# LVMi_Pressure_Sensor.net
KiCad netlist of a schematic drawn in EAGLE
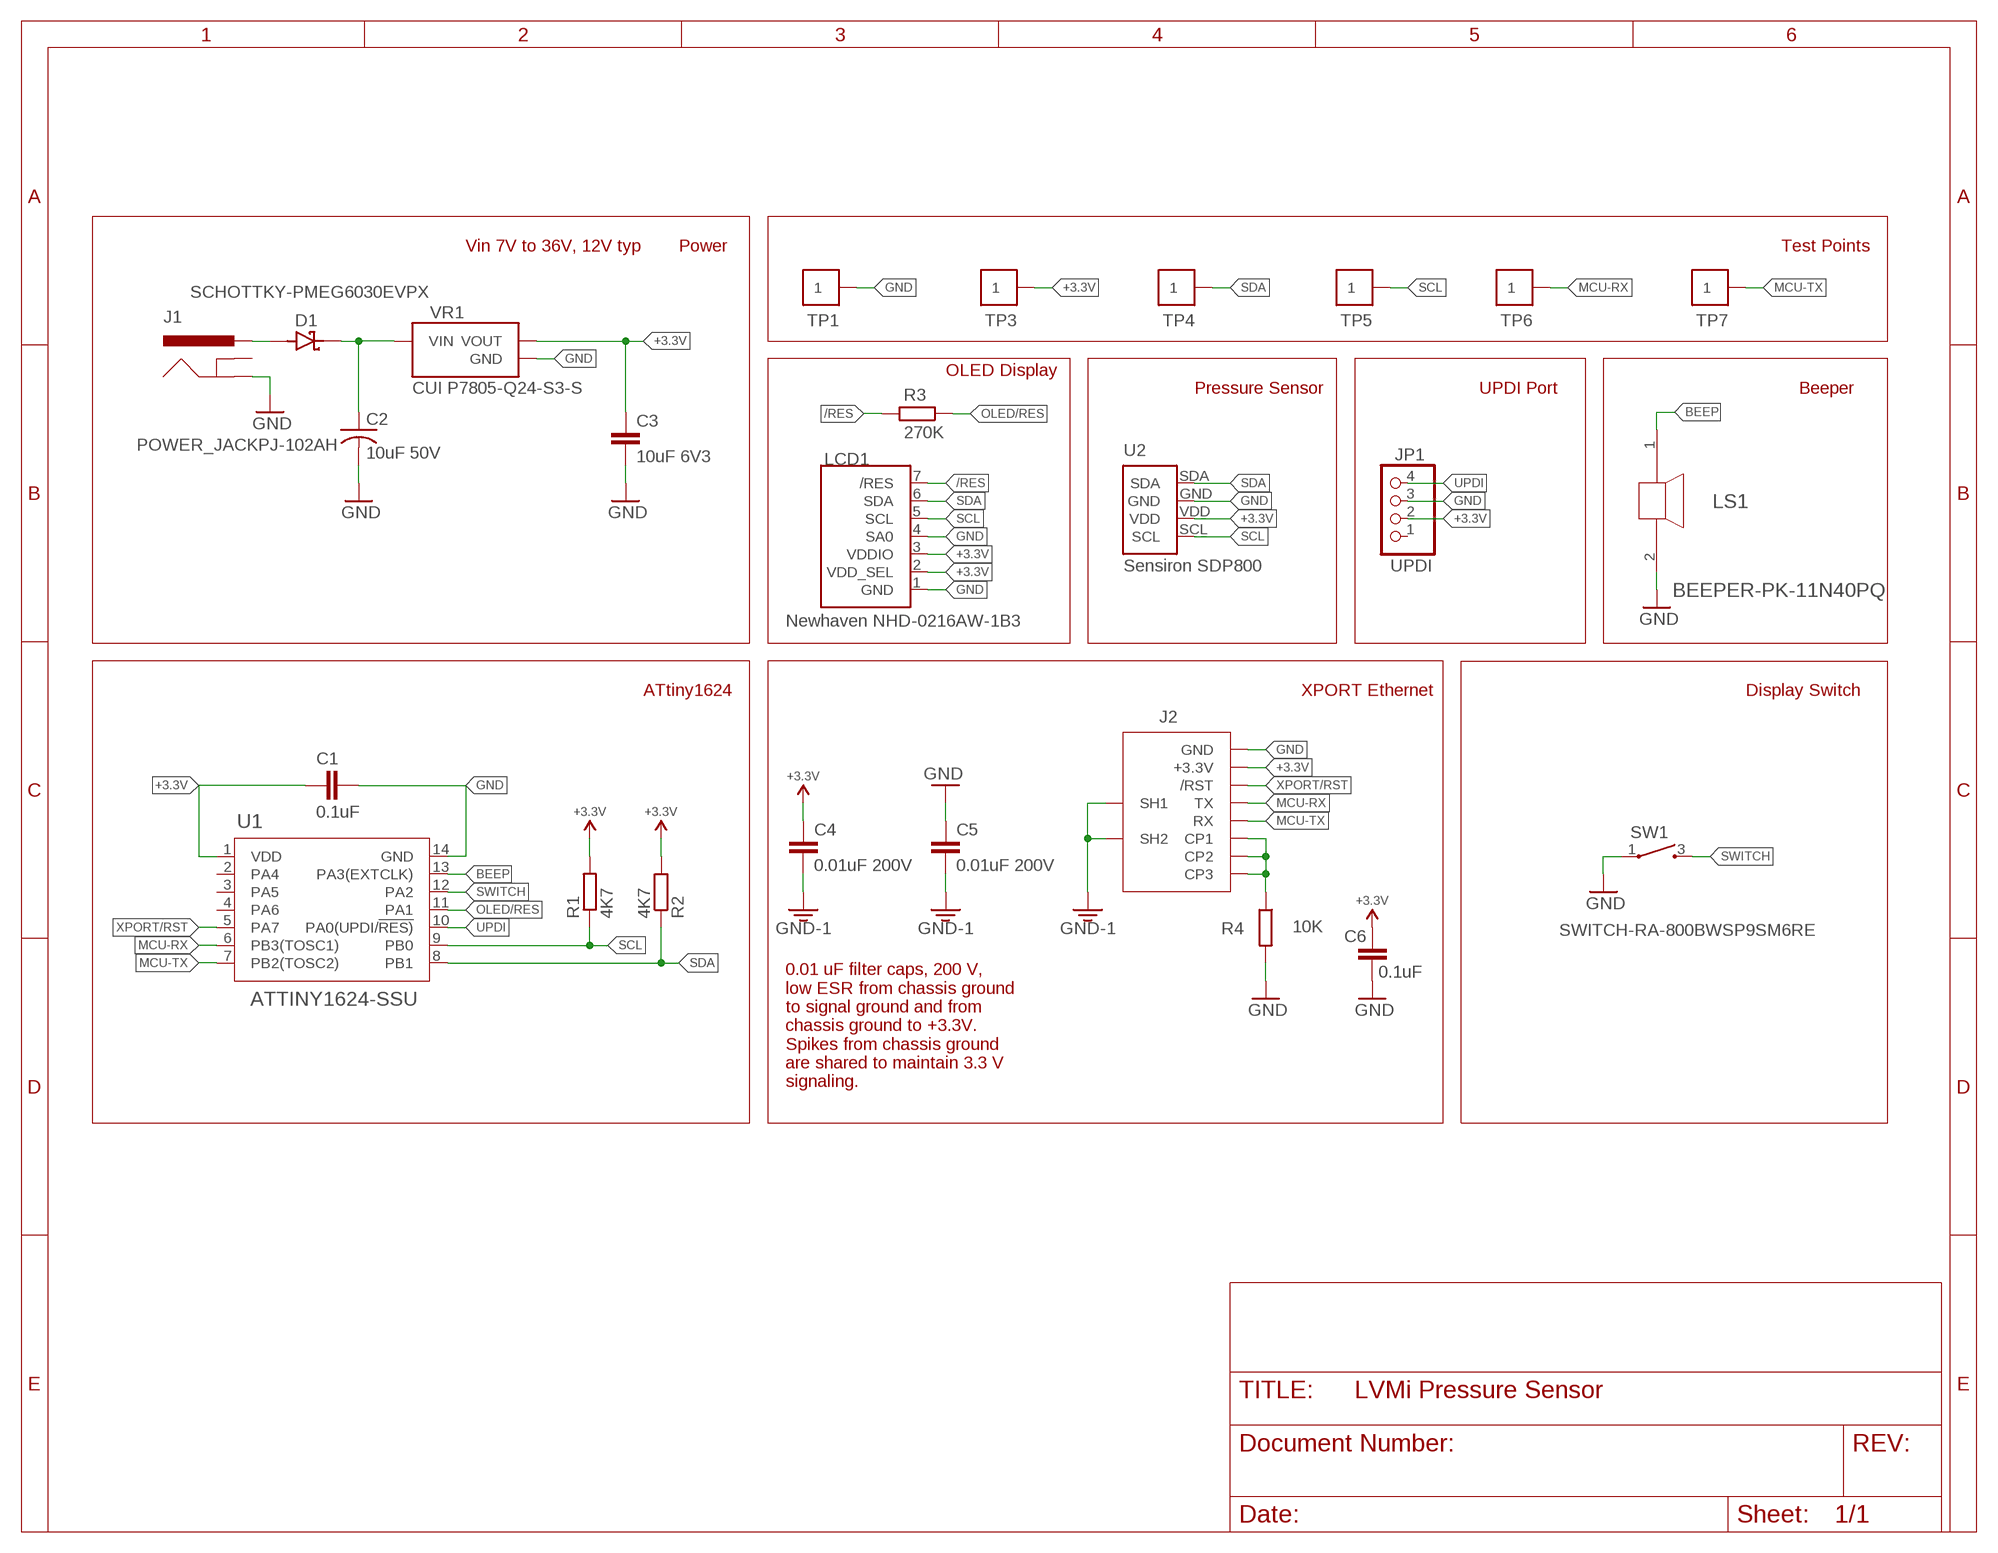
[diagram p0: schematic, sheet 1]

(export (version "E")
  (design (tool "Eeschema 10.0.6"))
  (components
    (comp (ref "C1")
      (value "0.1uF")
      (footprint "eagle-import:C0805")
      (libsource (lib "eagle-import") (part "C-EUC0805"))
    )
    (comp (ref "C2")
      (value "10uF 50V")
      (footprint "eagle-import:C1210")
      (libsource (lib "eagle-import") (part "C-USC1210"))
    )
    (comp (ref "C3")
      (value "10uF 6V3")
      (footprint "eagle-import:C0805")
      (libsource (lib "eagle-import") (part "C-EUC0805"))
    )
    (comp (ref "C4")
      (value "0.01uF 200V")
      (footprint "eagle-import:C0805")
      (libsource (lib "eagle-import") (part "C-EUC0805"))
    )
    (comp (ref "C5")
      (value "0.01uF 200V")
      (footprint "eagle-import:C0805")
      (libsource (lib "eagle-import") (part "C-EUC0805"))
    )
    (comp (ref "C6")
      (value "0.1uF")
      (footprint "eagle-import:C0805")
      (libsource (lib "eagle-import") (part "C-EUC0805"))
    )
    (comp (ref "D1")
      (value "SCHOTTKY-PMEG6030EVPX")
      (footprint "eagle-import:DIO_PMEG6030EVPX")
      (fields
        (field (name "DIGI-KEY_PART_NUMBER") "1727-1349-1-ND")
        (field (name "MF") "Nexperia USA")
        (field (name "MP") "PMEG6030EVPX")
      )
      (libsource (lib "eagle-import") (part "SCHOTTKY-PMEG6030EVPX"))
    )
    (comp (ref "J1")
      (value "POWER_JACKPJ-102AH")
      (footprint "eagle-import:PJ-102AH")
      (libsource (lib "eagle-import") (part "POWER_JACKPJ-102AH"))
    )
    (comp (ref "J2")
      (value "XPORTXPORT-2")
      (footprint "eagle-import:XPORT-2")
      (libsource (lib "eagle-import") (part "XPORTXPORT-2"))
    )
    (comp (ref "JP1")
      (value "UPDI")
      (footprint "eagle-import:1X04_90")
      (libsource (lib "eagle-import") (part "PINHD-1X4/90"))
    )
    (comp (ref "LCD1")
      (value "Newhaven NHD-0216AW-1B3")
      (footprint "eagle-import:LCD-NEWHAVEN-16X2")
      (libsource (lib "eagle-import") (part "LCD-NEWHAVEN-16X2"))
    )
    (comp (ref "LS1")
      (value "BEEPER-PK-11N40PQ")
      (footprint "eagle-import:PK-11N40PQ_MAL")
      (fields
        (field (name "MANUFACTURER_PART_NUMBER") "PK-11N40PQ")
        (field (name "COPYRIGHT") "Copyright (C) 2022 Ultra Librarian. All rights reserved.")
      )
      (libsource (lib "eagle-import") (part "BEEPER-PK-11N40PQ"))
    )
    (comp (ref "R1")
      (value "4K7")
      (footprint "eagle-import:R0805")
      (libsource (lib "eagle-import") (part "R-EU_R0805"))
    )
    (comp (ref "R2")
      (value "4K7")
      (footprint "eagle-import:R0805")
      (libsource (lib "eagle-import") (part "R-EU_R0805"))
    )
    (comp (ref "R3")
      (value "270K")
      (footprint "eagle-import:R0805")
      (libsource (lib "eagle-import") (part "R-EU_R0805"))
    )
    (comp (ref "R4")
      (value "10K")
      (footprint "eagle-import:R0805")
      (libsource (lib "eagle-import") (part "R-EU_R0805"))
    )
    (comp (ref "SW1")
      (value "SWITCH-RA-800BWSP9SM6RE")
      (footprint "eagle-import:SWITCH-RA-800BWSP9SM6RE")
      (libsource (lib "eagle-import") (part "SWITCH-RA-800BWSP9SM6RE"))
    )
    (comp (ref "TP1")
      (value "GND")
      (footprint "eagle-import:TP5000-TESTPOINT-BLK")
      (libsource (lib "eagle-import") (part "TP5000-TESTPOINT-BLK"))
    )
    (comp (ref "TP3")
      (value "+3.3V")
      (footprint "eagle-import:TP5000-TESTPOINT-PUR")
      (libsource (lib "eagle-import") (part "TP5000-TESTPOINT-PUR"))
    )
    (comp (ref "TP4")
      (value "SDA")
      (footprint "eagle-import:TP5000-TESTPOINT-YEL")
      (libsource (lib "eagle-import") (part "TP5000-TESTPOINT-YEL"))
    )
    (comp (ref "TP5")
      (value "SCL")
      (footprint "eagle-import:TP5000-TESTPOINT-WHI")
      (libsource (lib "eagle-import") (part "TP5000-TESTPOINT-WHI"))
    )
    (comp (ref "TP6")
      (value "MCU-RX")
      (footprint "eagle-import:TP5000-TESTPOINT-WHI")
      (libsource (lib "eagle-import") (part "TP5000-TESTPOINT-WHI"))
    )
    (comp (ref "TP7")
      (value "MCU-TX")
      (footprint "eagle-import:TP5000-TESTPOINT-WHI")
      (libsource (lib "eagle-import") (part "TP5000-TESTPOINT-WHI"))
    )
    (comp (ref "U1")
      (value "ATTINY1624-SSU")
      (footprint "eagle-import:SOIC150-14_MCH-M")
      (fields (field (name "COPYRIGHT") "Copyright (C) 2022 Ultra Librarian. All rights reserved."))
      (libsource (lib "eagle-import") (part "ATTINY1624-SSUSOIC150-14_MCH-M"))
    )
    (comp (ref "U2")
      (value "Sensiron SDP800")
      (footprint "eagle-import:SDP800_PRESSURE_SENSOR")
      (libsource (lib "eagle-import") (part "SDP800_PRESSURE_SENSOR"))
    )
    (comp (ref "VR1")
      (value "CUI P7805-Q24-S3-S")
      (footprint "eagle-import:CONV_P7805-Q24-S3-S")
      (fields (field (name "MF") "CUI") (field (name "MP") "P7805-Q12-S1R5-S"))
      (libsource (lib "eagle-import") (part "P7805-Q24-S3-S"))
    )
  )
  (nets
    (net (code "1") (name "+3.3V") (class "Default")
      (node (ref "C1") (pin "1") (pinfunction "1_1") (pintype "passive"))
      (node (ref "C3") (pin "1") (pinfunction "1_1") (pintype "passive"))
      (node (ref "C4") (pin "1") (pinfunction "1_1") (pintype "passive"))
      (node (ref "C6") (pin "2") (pinfunction "2_2") (pintype "passive"))
      (node (ref "J2") (pin "3.3V") (pinfunction "+3.3V_3.3V") (pintype "power_in"))
      (node (ref "JP1") (pin "2") (pinfunction "2_2") (pintype "passive"))
      (node (ref "LCD1") (pin "2") (pinfunction "VDD_SEL_2") (pintype "bidirectional"))
      (node (ref "LCD1") (pin "3") (pinfunction "VDDIO_3") (pintype "bidirectional"))
      (node (ref "R1") (pin "2") (pinfunction "2_2") (pintype "passive"))
      (node (ref "R2") (pin "2") (pinfunction "2_2") (pintype "passive"))
      (node (ref "TP3") (pin "P$1") (pinfunction "1_P$1") (pintype "bidirectional"))
      (node (ref "U1") (pin "1") (pinfunction "VDD_1") (pintype "power_in"))
      (node (ref "U2") (pin "VDD") (pinfunction "VDD_VDD") (pintype "bidirectional"))
      (node (ref "VR1") (pin "VOUT") (pinfunction "VOUT_VOUT") (pintype "power_in"))
    )
    (net (code "2") (name "BEEP") (class "Default")
      (node (ref "LS1") (pin "1") (pinfunction "1_1") (pintype "passive"))
      (node (ref "U1") (pin "13") (pinfunction "PA3(EXTCLK)_13") (pintype "bidirectional"))
    )
    (net (code "3") (name "GND") (class "Default")
      (node (ref "C1") (pin "2") (pinfunction "2_2") (pintype "passive"))
      (node (ref "C2") (pin "2") (pinfunction "2_2") (pintype "passive"))
      (node (ref "C3") (pin "2") (pinfunction "2_2") (pintype "passive"))
      (node (ref "C5") (pin "1") (pinfunction "1_1") (pintype "passive"))
      (node (ref "C6") (pin "1") (pinfunction "1_1") (pintype "passive"))
      (node (ref "J1") (pin "GND") (pinfunction "GND_GND") (pintype "bidirectional"))
      (node (ref "J2") (pin "GND") (pinfunction "GND_GND") (pintype "power_in"))
      (node (ref "JP1") (pin "3") (pinfunction "3_3") (pintype "passive"))
      (node (ref "LCD1") (pin "1") (pinfunction "GND_1") (pintype "bidirectional"))
      (node (ref "LCD1") (pin "4") (pinfunction "SA0_4") (pintype "bidirectional"))
      (node (ref "LS1") (pin "2") (pinfunction "2_2") (pintype "passive"))
      (node (ref "R4") (pin "2") (pinfunction "2_2") (pintype "passive"))
      (node (ref "SW1") (pin "1") (pinfunction "1_1") (pintype "passive"))
      (node (ref "TP1") (pin "P$1") (pinfunction "1_P$1") (pintype "bidirectional"))
      (node (ref "U1") (pin "14") (pinfunction "GND_14") (pintype "passive"))
      (node (ref "U2") (pin "GND") (pinfunction "GND_GND") (pintype "bidirectional"))
      (node (ref "VR1") (pin "GND") (pinfunction "GND_GND") (pintype "power_in"))
    )
    (net (code "4") (name "GND-1") (class "Default")
      (node (ref "C4") (pin "2") (pinfunction "2_2") (pintype "passive"))
      (node (ref "C5") (pin "2") (pinfunction "2_2") (pintype "passive"))
      (node (ref "J2") (pin "P$1") (pinfunction "SH1_P$1") (pintype "bidirectional"))
      (node (ref "J2") (pin "P$2") (pinfunction "SH2_P$2") (pintype "bidirectional"))
    )
    (net (code "5") (name "MCU-RX") (class "Default")
      (node (ref "J2") (pin "TX") (pinfunction "TX_TX") (pintype "output"))
      (node (ref "TP6") (pin "P$1") (pinfunction "1_P$1") (pintype "bidirectional"))
      (node (ref "U1") (pin "6") (pinfunction "PB3(TOSC1)_6") (pintype "bidirectional"))
    )
    (net (code "6") (name "MCU-TX") (class "Default")
      (node (ref "J2") (pin "RX") (pinfunction "RX_RX") (pintype "input"))
      (node (ref "TP7") (pin "P$1") (pinfunction "1_P$1") (pintype "bidirectional"))
      (node (ref "U1") (pin "7") (pinfunction "PB2(TOSC2)_7") (pintype "bidirectional"))
    )
    (net (code "7") (name "Net-(D1-A)") (class "Default")
      (node (ref "D1") (pin "2") (pinfunction "A_2") (pintype "passive"))
      (node (ref "J1") (pin "PWR") (pinfunction "PWR_PWR") (pintype "bidirectional"))
    )
    (net (code "8") (name "Net-(D1-K)") (class "Default")
      (node (ref "C2") (pin "1") (pinfunction "1_1") (pintype "passive"))
      (node (ref "D1") (pin "1") (pinfunction "K_1") (pintype "passive"))
      (node (ref "VR1") (pin "VIN") (pinfunction "VIN_VIN") (pintype "power_in"))
    )
    (net (code "9") (name "Net-(J2-PadCP1)") (class "Default")
      (node (ref "J2") (pin "CP1") (pinfunction "CP1_CP1") (pintype "bidirectional"))
      (node (ref "J2") (pin "CP2") (pinfunction "CP2_CP2") (pintype "bidirectional"))
      (node (ref "J2") (pin "CP3") (pinfunction "CP3_CP3") (pintype "bidirectional"))
      (node (ref "R4") (pin "1") (pinfunction "1_1") (pintype "passive"))
    )
    (net (code "10") (name "OLED{slash}RES") (class "Default")
      (node (ref "R3") (pin "1") (pinfunction "1_1") (pintype "passive"))
      (node (ref "U1") (pin "11") (pinfunction "PA1_11") (pintype "bidirectional"))
    )
    (net (code "11") (name "SCL") (class "Default")
      (node (ref "LCD1") (pin "5") (pinfunction "SCL_5") (pintype "bidirectional"))
      (node (ref "R1") (pin "1") (pinfunction "1_1") (pintype "passive"))
      (node (ref "TP5") (pin "P$1") (pinfunction "1_P$1") (pintype "bidirectional"))
      (node (ref "U1") (pin "9") (pinfunction "PB0_9") (pintype "bidirectional"))
      (node (ref "U2") (pin "SCL") (pinfunction "SCL_SCL") (pintype "bidirectional"))
    )
    (net (code "12") (name "SDA") (class "Default")
      (node (ref "LCD1") (pin "6") (pinfunction "SDA_6") (pintype "bidirectional"))
      (node (ref "R2") (pin "1") (pinfunction "1_1") (pintype "passive"))
      (node (ref "TP4") (pin "P$1") (pinfunction "1_P$1") (pintype "bidirectional"))
      (node (ref "U1") (pin "8") (pinfunction "PB1_8") (pintype "bidirectional"))
      (node (ref "U2") (pin "SDA") (pinfunction "SDA_SDA") (pintype "bidirectional"))
    )
    (net (code "13") (name "SWITCH") (class "Default")
      (node (ref "SW1") (pin "3") (pinfunction "2_3") (pintype "passive"))
      (node (ref "U1") (pin "12") (pinfunction "PA2_12") (pintype "bidirectional"))
    )
    (net (code "14") (name "UPDI") (class "Default")
      (node (ref "JP1") (pin "4") (pinfunction "4_4") (pintype "passive"))
      (node (ref "U1") (pin "10") (pinfunction "PA0(UPDI/~{RES})_10") (pintype "bidirectional"))
    )
    (net (code "15") (name "XPORT{slash}RST") (class "Default")
      (node (ref "J2") (pin "/RST") (pinfunction "/RST_/RST") (pintype "input"))
      (node (ref "U1") (pin "5") (pinfunction "PA7_5") (pintype "bidirectional"))
    )
    (net (code "16") (name "unconnected-(J1-GNDBREAK-PadGNDBRK)") (class "Default")
      (node (ref "J1") (pin "GNDBRK") (pinfunction "GNDBREAK_GNDBRK") (pintype "bidirectional"))
    )
    (net (code "17") (name "unconnected-(JP1-Pad1)") (class "Default")
      (node (ref "JP1") (pin "1") (pinfunction "1_1") (pintype "passive"))
    )
    (net (code "18") (name "unconnected-(U1-PA4-Pad2)") (class "Default")
      (node (ref "U1") (pin "2") (pinfunction "PA4_2") (pintype "bidirectional"))
    )
    (net (code "19") (name "unconnected-(U1-PA5-Pad3)") (class "Default")
      (node (ref "U1") (pin "3") (pinfunction "PA5_3") (pintype "bidirectional"))
    )
    (net (code "20") (name "unconnected-(U1-PA6-Pad4)") (class "Default")
      (node (ref "U1") (pin "4") (pinfunction "PA6_4") (pintype "bidirectional"))
    )
    (net (code "21") (name "{slash}RES") (class "Default")
      (node (ref "LCD1") (pin "7") (pinfunction "/RES_7") (pintype "bidirectional"))
      (node (ref "R3") (pin "2") (pinfunction "2_2") (pintype "passive"))
    )
  )
)
